# CommonBoard_FK_H743_out.net
KiCad netlist of a schematic drawn in Altium Designer
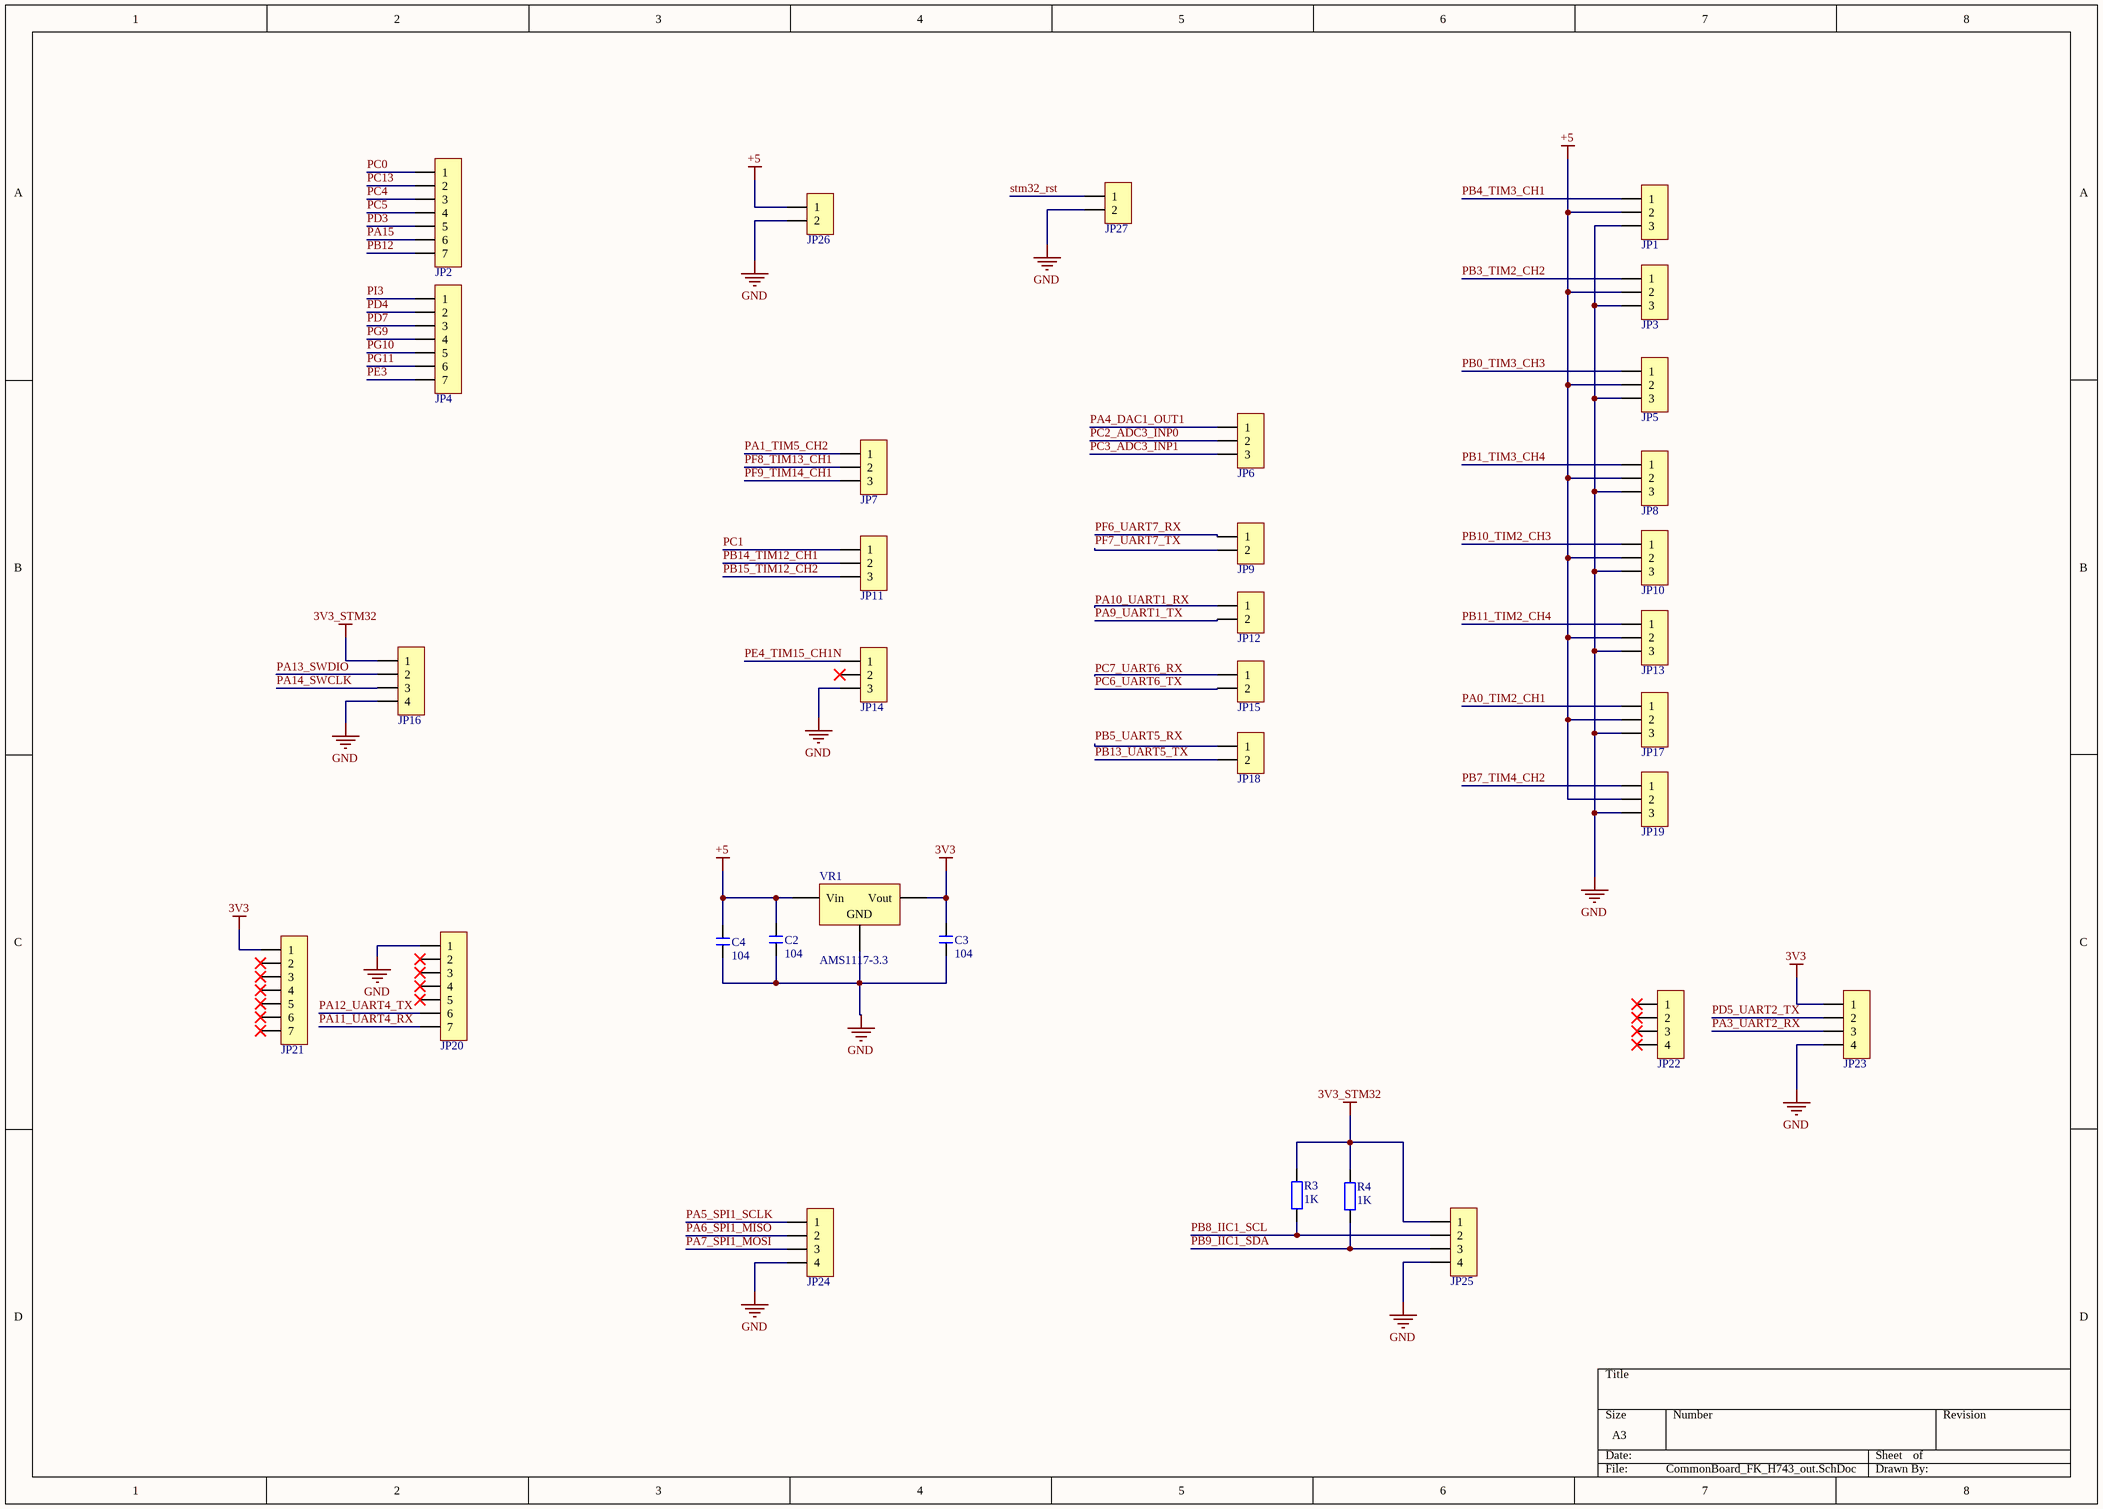
[diagram p0: CommonBoard_FK_H743_out.SchDoc]

(export (version "E")
  (design (tool "Eeschema 10.0.6"))
  (components
    (comp (ref "C2")
      (value "104")
      (footprint "C 0603_L")
      (description "无极性贴片电容")
      (fields (field (name "版权归属") "源创客"))
      (libsource (lib "3.1   - 电阻-电容-电感") (part "C"))
    )
    (comp (ref "C3")
      (value "104")
      (footprint "C 0603_L")
      (description "无极性贴片电容")
      (fields (field (name "版权归属") "源创客"))
      (libsource (lib "3.1   - 电阻-电容-电感") (part "C"))
    )
    (comp (ref "C4")
      (value "104")
      (footprint "C 0603_L")
      (description "无极性贴片电容")
      (fields (field (name "版权归属") "源创客"))
      (libsource (lib "3.1   - 电阻-电容-电感") (part "C"))
    )
    (comp (ref "JP1")
      (value "HDR-1X3")
      (footprint "HDR2.54-LI-3P")
      (description "3P接插件")
      (fields (field (name "版权归属") "源创客"))
      (libsource (lib "4.5   - 接插件-脚距2.54") (part "Header 3"))
    )
    (comp (ref "JP2")
      (value "HDR-1X7")
      (footprint "HDR2.54-LI-7P")
      (description "7P接插件")
      (fields (field (name "版权归属") "源创客"))
      (libsource (lib "4.5   - 接插件-脚距2.54") (part "Header 7"))
    )
    (comp (ref "JP3")
      (value "HDR-1X3")
      (footprint "HDR2.54-LI-3P")
      (description "3P接插件")
      (fields (field (name "版权归属") "源创客"))
      (libsource (lib "4.5   - 接插件-脚距2.54") (part "Header 3"))
    )
    (comp (ref "JP4")
      (value "HDR-1X7")
      (footprint "HDR2.54-LI-7P")
      (description "7P接插件")
      (fields (field (name "版权归属") "源创客"))
      (libsource (lib "4.5   - 接插件-脚距2.54") (part "Header 7"))
    )
    (comp (ref "JP5")
      (value "HDR-1X3")
      (footprint "HDR2.54-LI-3P")
      (description "3P接插件")
      (fields (field (name "版权归属") "源创客"))
      (libsource (lib "4.5   - 接插件-脚距2.54") (part "Header 3"))
    )
    (comp (ref "JP6")
      (value "HDR-1X3")
      (footprint "HDR2.54-LI-3P")
      (description "3P接插件")
      (fields (field (name "版权归属") "源创客"))
      (libsource (lib "4.5   - 接插件-脚距2.54") (part "Header 3"))
    )
    (comp (ref "JP7")
      (value "HDR-1X3")
      (footprint "HDR2.54-LI-3P")
      (description "3P接插件")
      (fields (field (name "版权归属") "源创客"))
      (libsource (lib "4.5   - 接插件-脚距2.54") (part "Header 3"))
    )
    (comp (ref "JP8")
      (value "HDR-1X3")
      (footprint "HDR2.54-LI-3P")
      (description "3P接插件")
      (fields (field (name "版权归属") "源创客"))
      (libsource (lib "4.5   - 接插件-脚距2.54") (part "Header 3"))
    )
    (comp (ref "JP9")
      (value "HDR-1X2")
      (footprint "HDR2.54-LI-2P")
      (description "2P接插件")
      (fields (field (name "版权归属") "源创客"))
      (libsource (lib "4.5   - 接插件-脚距2.54") (part "Header 2"))
    )
    (comp (ref "JP10")
      (value "HDR-1X3")
      (footprint "HDR2.54-LI-3P")
      (description "3P接插件")
      (fields (field (name "版权归属") "源创客"))
      (libsource (lib "4.5   - 接插件-脚距2.54") (part "Header 3"))
    )
    (comp (ref "JP11")
      (value "HDR-1X3")
      (footprint "HDR2.54-LI-3P")
      (description "3P接插件")
      (fields (field (name "版权归属") "源创客"))
      (libsource (lib "4.5   - 接插件-脚距2.54") (part "Header 3"))
    )
    (comp (ref "JP12")
      (value "HDR-1X2")
      (footprint "HDR2.54-LI-2P")
      (description "2P接插件")
      (fields (field (name "版权归属") "源创客"))
      (libsource (lib "4.5   - 接插件-脚距2.54") (part "Header 2"))
    )
    (comp (ref "JP13")
      (value "HDR-1X3")
      (footprint "HDR2.54-LI-3P")
      (description "3P接插件")
      (fields (field (name "版权归属") "源创客"))
      (libsource (lib "4.5   - 接插件-脚距2.54") (part "Header 3"))
    )
    (comp (ref "JP14")
      (value "HDR-1X3")
      (footprint "HDR2.54-LI-3P")
      (description "3P接插件")
      (fields (field (name "版权归属") "源创客"))
      (libsource (lib "4.5   - 接插件-脚距2.54") (part "Header 3"))
    )
    (comp (ref "JP15")
      (value "HDR-1X2")
      (footprint "HDR2.54-LI-2P")
      (description "2P接插件")
      (fields (field (name "版权归属") "源创客"))
      (libsource (lib "4.5   - 接插件-脚距2.54") (part "Header 2"))
    )
    (comp (ref "JP16")
      (value "HDR-1X4")
      (footprint "HDR2.54-LI-4P")
      (description "4P接插件")
      (fields (field (name "版权归属") "源创客"))
      (libsource (lib "4.5   - 接插件-脚距2.54") (part "Header 4"))
    )
    (comp (ref "JP17")
      (value "HDR-1X3")
      (footprint "HDR2.54-LI-3P")
      (description "3P接插件")
      (fields (field (name "版权归属") "源创客"))
      (libsource (lib "4.5   - 接插件-脚距2.54") (part "Header 3"))
    )
    (comp (ref "JP18")
      (value "HDR-1X2")
      (footprint "HDR2.54-LI-2P")
      (description "2P接插件")
      (fields (field (name "版权归属") "源创客"))
      (libsource (lib "4.5   - 接插件-脚距2.54") (part "Header 2"))
    )
    (comp (ref "JP19")
      (value "HDR-1X3")
      (footprint "HDR2.54-LI-3P")
      (description "3P接插件")
      (fields (field (name "版权归属") "源创客"))
      (libsource (lib "4.5   - 接插件-脚距2.54") (part "Header 3"))
    )
    (comp (ref "JP20")
      (value "HDR-1X7")
      (footprint "HDR2.54-LI-7P")
      (description "7P接插件")
      (fields (field (name "版权归属") "源创客"))
      (libsource (lib "4.5   - 接插件-脚距2.54") (part "Header 7"))
    )
    (comp (ref "JP21")
      (value "HDR-1X7")
      (footprint "HDR2.54-LI-7P")
      (description "7P接插件")
      (fields (field (name "版权归属") "源创客"))
      (libsource (lib "4.5   - 接插件-脚距2.54") (part "Header 7"))
    )
    (comp (ref "JP22")
      (value "HDR-1X4")
      (footprint "HDR2.54-LI-4P")
      (description "4P接插件")
      (fields (field (name "版权归属") "源创客"))
      (libsource (lib "4.5   - 接插件-脚距2.54") (part "Header 4"))
    )
    (comp (ref "JP23")
      (value "HDR-1X4")
      (footprint "HDR2.54-LI-4P")
      (description "4P接插件")
      (fields (field (name "版权归属") "源创客"))
      (libsource (lib "4.5   - 接插件-脚距2.54") (part "Header 4"))
    )
    (comp (ref "JP24")
      (value "HDR-1X4")
      (footprint "HDR2.54-LI-4P")
      (description "4P接插件")
      (fields (field (name "版权归属") "源创客"))
      (libsource (lib "4.5   - 接插件-脚距2.54") (part "Header 4"))
    )
    (comp (ref "JP25")
      (value "HDR-1X4")
      (footprint "HDR2.54-LI-4P")
      (description "4P接插件")
      (fields (field (name "版权归属") "源创客"))
      (libsource (lib "4.5   - 接插件-脚距2.54") (part "Header 4"))
    )
    (comp (ref "JP26")
      (value "HDR-1X2")
      (footprint "KF128-3.81-2P")
      (description "2P接插件")
      (fields (field (name "版权归属") "源创客"))
      (libsource (lib "4.7   - 接插件-脚距3.81") (part "Header 2"))
    )
    (comp (ref "JP27")
      (value "HDR-1X2")
      (footprint "HDR2.54-LI-2P")
      (description "2P接插件")
      (fields (field (name "版权归属") "源创客"))
      (libsource (lib "4.5   - 接插件-脚距2.54") (part "Header 2"))
    )
    (comp (ref "R3")
      (value "1K")
      (footprint "R 0603_L")
      (description "贴片电阻")
      (fields (field (name "版权归属") "源创客"))
      (libsource (lib "3.1   - 电阻-电容-电感") (part "R"))
    )
    (comp (ref "R4")
      (value "1K")
      (footprint "R 0603_L")
      (description "贴片电阻")
      (fields (field (name "版权归属") "源创客"))
      (libsource (lib "3.1   - 电阻-电容-电感") (part "R"))
    )
    (comp (ref "VR1")
      (value "AMS1117-3.3")
      (footprint "SOT-223")
      (description "低压差线性稳压(LDO)")
      (libsource (lib "Miscellaneous Devices LC") (part "SOT-223 AMS1117-3.3"))
    )
  )
  (nets
    (net (code "1") (name "+5") (class "Default")
      (node (ref "C2") (pin "2") (pinfunction "2_2") (pintype "passive"))
      (node (ref "C4") (pin "2") (pinfunction "2_2") (pintype "passive"))
      (node (ref "JP1") (pin "2") (pinfunction "2_2") (pintype "passive"))
      (node (ref "JP10") (pin "2") (pinfunction "2_2") (pintype "passive"))
      (node (ref "JP13") (pin "2") (pinfunction "2_2") (pintype "passive"))
      (node (ref "JP17") (pin "2") (pinfunction "2_2") (pintype "passive"))
      (node (ref "JP19") (pin "2") (pinfunction "2_2") (pintype "passive"))
      (node (ref "JP26") (pin "1") (pinfunction "1_1") (pintype "passive"))
      (node (ref "JP3") (pin "2") (pinfunction "2_2") (pintype "passive"))
      (node (ref "JP5") (pin "2") (pinfunction "2_2") (pintype "passive"))
      (node (ref "JP8") (pin "2") (pinfunction "2_2") (pintype "passive"))
      (node (ref "VR1") (pin "3") (pinfunction "Vin_3") (pintype "passive"))
    )
    (net (code "2") (name "/PA0_TIM2_CH1") (class "Default")
      (node (ref "JP17") (pin "1") (pinfunction "1_1") (pintype "passive"))
    )
    (net (code "3") (name "/PA1_TIM5_CH2") (class "Default")
      (node (ref "JP7") (pin "1") (pinfunction "1_1") (pintype "passive"))
    )
    (net (code "4") (name "/PA3_UART2_RX") (class "Default")
      (node (ref "JP23") (pin "3") (pinfunction "3_3") (pintype "passive"))
    )
    (net (code "5") (name "/PA4_DAC1_OUT1") (class "Default")
      (node (ref "JP6") (pin "1") (pinfunction "1_1") (pintype "passive"))
    )
    (net (code "6") (name "/PA5_SPI1_SCLK") (class "Default")
      (node (ref "JP24") (pin "1") (pinfunction "1_1") (pintype "passive"))
    )
    (net (code "7") (name "/PA6_SPI1_MISO") (class "Default")
      (node (ref "JP24") (pin "2") (pinfunction "2_2") (pintype "passive"))
    )
    (net (code "8") (name "/PA7_SPI1_MOSI") (class "Default")
      (node (ref "JP24") (pin "3") (pinfunction "3_3") (pintype "passive"))
    )
    (net (code "9") (name "/PA9_UART1_TX") (class "Default")
      (node (ref "JP12") (pin "2") (pinfunction "2_2") (pintype "passive"))
    )
    (net (code "10") (name "/PA10_UART1_RX") (class "Default")
      (node (ref "JP12") (pin "1") (pinfunction "1_1") (pintype "passive"))
    )
    (net (code "11") (name "/PA11_UART4_RX") (class "Default")
      (node (ref "JP20") (pin "7") (pinfunction "7_7") (pintype "passive"))
    )
    (net (code "12") (name "/PA12_UART4_TX") (class "Default")
      (node (ref "JP20") (pin "6") (pinfunction "6_6") (pintype "passive"))
    )
    (net (code "13") (name "/PA13_SWDIO") (class "Default")
      (node (ref "JP16") (pin "2") (pinfunction "2_2") (pintype "passive"))
    )
    (net (code "14") (name "/PA14_SWCLK") (class "Default")
      (node (ref "JP16") (pin "3") (pinfunction "3_3") (pintype "passive"))
    )
    (net (code "15") (name "/PA15") (class "Default")
      (node (ref "JP2") (pin "6") (pinfunction "6_6") (pintype "passive"))
    )
    (net (code "16") (name "/PB0_TIM3_CH3") (class "Default")
      (node (ref "JP5") (pin "1") (pinfunction "1_1") (pintype "passive"))
    )
    (net (code "17") (name "/PB1_TIM3_CH4") (class "Default")
      (node (ref "JP8") (pin "1") (pinfunction "1_1") (pintype "passive"))
    )
    (net (code "18") (name "/PB3_TIM2_CH2") (class "Default")
      (node (ref "JP3") (pin "1") (pinfunction "1_1") (pintype "passive"))
    )
    (net (code "19") (name "/PB4_TIM3_CH1") (class "Default")
      (node (ref "JP1") (pin "1") (pinfunction "1_1") (pintype "passive"))
    )
    (net (code "20") (name "/PB5_UART5_RX") (class "Default")
      (node (ref "JP18") (pin "1") (pinfunction "1_1") (pintype "passive"))
    )
    (net (code "21") (name "/PB7_TIM4_CH2") (class "Default")
      (node (ref "JP19") (pin "1") (pinfunction "1_1") (pintype "passive"))
    )
    (net (code "22") (name "/PB8_IIC1_SCL") (class "Default")
      (node (ref "JP25") (pin "2") (pinfunction "2_2") (pintype "passive"))
      (node (ref "R3") (pin "2") (pinfunction "2_2") (pintype "passive"))
    )
    (net (code "23") (name "/PB9_IIC1_SDA") (class "Default")
      (node (ref "JP25") (pin "3") (pinfunction "3_3") (pintype "passive"))
      (node (ref "R4") (pin "2") (pinfunction "2_2") (pintype "passive"))
    )
    (net (code "24") (name "/PB10_TIM2_CH3") (class "Default")
      (node (ref "JP10") (pin "1") (pinfunction "1_1") (pintype "passive"))
    )
    (net (code "25") (name "/PB11_TIM2_CH4") (class "Default")
      (node (ref "JP13") (pin "1") (pinfunction "1_1") (pintype "passive"))
    )
    (net (code "26") (name "/PB12") (class "Default")
      (node (ref "JP2") (pin "7") (pinfunction "7_7") (pintype "passive"))
    )
    (net (code "27") (name "/PB13_UART5_TX") (class "Default")
      (node (ref "JP18") (pin "2") (pinfunction "2_2") (pintype "passive"))
    )
    (net (code "28") (name "/PB14_TIM12_CH1") (class "Default")
      (node (ref "JP11") (pin "2") (pinfunction "2_2") (pintype "passive"))
    )
    (net (code "29") (name "/PB15_TIM12_CH2") (class "Default")
      (node (ref "JP11") (pin "3") (pinfunction "3_3") (pintype "passive"))
    )
    (net (code "30") (name "/PC0") (class "Default")
      (node (ref "JP2") (pin "1") (pinfunction "1_1") (pintype "passive"))
    )
    (net (code "31") (name "/PC1") (class "Default")
      (node (ref "JP11") (pin "1") (pinfunction "1_1") (pintype "passive"))
    )
    (net (code "32") (name "/PC2_ADC3_INP0") (class "Default")
      (node (ref "JP6") (pin "2") (pinfunction "2_2") (pintype "passive"))
    )
    (net (code "33") (name "/PC3_ADC3_INP1") (class "Default")
      (node (ref "JP6") (pin "3") (pinfunction "3_3") (pintype "passive"))
    )
    (net (code "34") (name "/PC4") (class "Default")
      (node (ref "JP2") (pin "3") (pinfunction "3_3") (pintype "passive"))
    )
    (net (code "35") (name "/PC5") (class "Default")
      (node (ref "JP2") (pin "4") (pinfunction "4_4") (pintype "passive"))
    )
    (net (code "36") (name "/PC6_UART6_TX") (class "Default")
      (node (ref "JP15") (pin "2") (pinfunction "2_2") (pintype "passive"))
    )
    (net (code "37") (name "/PC7_UART6_RX") (class "Default")
      (node (ref "JP15") (pin "1") (pinfunction "1_1") (pintype "passive"))
    )
    (net (code "38") (name "/PC13") (class "Default")
      (node (ref "JP2") (pin "2") (pinfunction "2_2") (pintype "passive"))
    )
    (net (code "39") (name "/PD3") (class "Default")
      (node (ref "JP2") (pin "5") (pinfunction "5_5") (pintype "passive"))
    )
    (net (code "40") (name "/PD4") (class "Default")
      (node (ref "JP4") (pin "2") (pinfunction "2_2") (pintype "passive"))
    )
    (net (code "41") (name "/PD5_UART2_TX") (class "Default")
      (node (ref "JP23") (pin "2") (pinfunction "2_2") (pintype "passive"))
    )
    (net (code "42") (name "/PD7") (class "Default")
      (node (ref "JP4") (pin "3") (pinfunction "3_3") (pintype "passive"))
    )
    (net (code "43") (name "/PE3") (class "Default")
      (node (ref "JP4") (pin "7") (pinfunction "7_7") (pintype "passive"))
    )
    (net (code "44") (name "/PE4_TIM15_CH1N") (class "Default")
      (node (ref "JP14") (pin "1") (pinfunction "1_1") (pintype "passive"))
    )
    (net (code "45") (name "/PF6_UART7_RX") (class "Default")
      (node (ref "JP9") (pin "1") (pinfunction "1_1") (pintype "passive"))
    )
    (net (code "46") (name "/PF7_UART7_TX") (class "Default")
      (node (ref "JP9") (pin "2") (pinfunction "2_2") (pintype "passive"))
    )
    (net (code "47") (name "/PF8_TIM13_CH1") (class "Default")
      (node (ref "JP7") (pin "2") (pinfunction "2_2") (pintype "passive"))
    )
    (net (code "48") (name "/PF9_TIM14_CH1") (class "Default")
      (node (ref "JP7") (pin "3") (pinfunction "3_3") (pintype "passive"))
    )
    (net (code "49") (name "/PG9") (class "Default")
      (node (ref "JP4") (pin "4") (pinfunction "4_4") (pintype "passive"))
    )
    (net (code "50") (name "/PG10") (class "Default")
      (node (ref "JP4") (pin "5") (pinfunction "5_5") (pintype "passive"))
    )
    (net (code "51") (name "/PG11") (class "Default")
      (node (ref "JP4") (pin "6") (pinfunction "6_6") (pintype "passive"))
    )
    (net (code "52") (name "/PI3") (class "Default")
      (node (ref "JP4") (pin "1") (pinfunction "1_1") (pintype "passive"))
    )
    (net (code "53") (name "/stm32_rst") (class "Default")
      (node (ref "JP27") (pin "1") (pinfunction "1_1") (pintype "passive"))
    )
    (net (code "54") (name "3V3") (class "Default")
      (node (ref "C3") (pin "2") (pinfunction "2_2") (pintype "passive"))
      (node (ref "JP21") (pin "1") (pinfunction "1_1") (pintype "passive"))
      (node (ref "JP23") (pin "1") (pinfunction "1_1") (pintype "passive"))
      (node (ref "VR1") (pin "2") (pinfunction "Vout_2") (pintype "passive"))
    )
    (net (code "55") (name "3V3_STM32") (class "Default")
      (node (ref "JP16") (pin "1") (pinfunction "1_1") (pintype "passive"))
      (node (ref "JP25") (pin "1") (pinfunction "1_1") (pintype "passive"))
      (node (ref "R3") (pin "1") (pinfunction "1_1") (pintype "passive"))
      (node (ref "R4") (pin "1") (pinfunction "1_1") (pintype "passive"))
    )
    (net (code "56") (name "GND") (class "Default")
      (node (ref "C2") (pin "1") (pinfunction "1_1") (pintype "passive"))
      (node (ref "C3") (pin "1") (pinfunction "1_1") (pintype "passive"))
      (node (ref "C4") (pin "1") (pinfunction "1_1") (pintype "passive"))
      (node (ref "JP1") (pin "3") (pinfunction "3_3") (pintype "passive"))
      (node (ref "JP10") (pin "3") (pinfunction "3_3") (pintype "passive"))
      (node (ref "JP13") (pin "3") (pinfunction "3_3") (pintype "passive"))
      (node (ref "JP14") (pin "3") (pinfunction "3_3") (pintype "passive"))
      (node (ref "JP16") (pin "4") (pinfunction "4_4") (pintype "passive"))
      (node (ref "JP17") (pin "3") (pinfunction "3_3") (pintype "passive"))
      (node (ref "JP19") (pin "3") (pinfunction "3_3") (pintype "passive"))
      (node (ref "JP20") (pin "1") (pinfunction "1_1") (pintype "passive"))
      (node (ref "JP23") (pin "4") (pinfunction "4_4") (pintype "passive"))
      (node (ref "JP24") (pin "4") (pinfunction "4_4") (pintype "passive"))
      (node (ref "JP25") (pin "4") (pinfunction "4_4") (pintype "passive"))
      (node (ref "JP26") (pin "2") (pinfunction "2_2") (pintype "passive"))
      (node (ref "JP27") (pin "2") (pinfunction "2_2") (pintype "passive"))
      (node (ref "JP3") (pin "3") (pinfunction "3_3") (pintype "passive"))
      (node (ref "JP5") (pin "3") (pinfunction "3_3") (pintype "passive"))
      (node (ref "JP8") (pin "3") (pinfunction "3_3") (pintype "passive"))
      (node (ref "VR1") (pin "1") (pinfunction "GND_1") (pintype "passive"))
    )
    (net (code "57") (name "unconnected-(JP14-Pad2)") (class "Default")
      (node (ref "JP14") (pin "2") (pinfunction "2_2") (pintype "passive+no_connect"))
    )
    (net (code "58") (name "unconnected-(JP20-Pad2)") (class "Default")
      (node (ref "JP20") (pin "2") (pinfunction "2_2") (pintype "passive+no_connect"))
    )
    (net (code "59") (name "unconnected-(JP20-Pad3)") (class "Default")
      (node (ref "JP20") (pin "3") (pinfunction "3_3") (pintype "passive+no_connect"))
    )
    (net (code "60") (name "unconnected-(JP20-Pad4)") (class "Default")
      (node (ref "JP20") (pin "4") (pinfunction "4_4") (pintype "passive+no_connect"))
    )
    (net (code "61") (name "unconnected-(JP20-Pad5)") (class "Default")
      (node (ref "JP20") (pin "5") (pinfunction "5_5") (pintype "passive+no_connect"))
    )
    (net (code "62") (name "unconnected-(JP21-Pad2)") (class "Default")
      (node (ref "JP21") (pin "2") (pinfunction "2_2") (pintype "passive+no_connect"))
    )
    (net (code "63") (name "unconnected-(JP21-Pad3)") (class "Default")
      (node (ref "JP21") (pin "3") (pinfunction "3_3") (pintype "passive+no_connect"))
    )
    (net (code "64") (name "unconnected-(JP21-Pad4)") (class "Default")
      (node (ref "JP21") (pin "4") (pinfunction "4_4") (pintype "passive+no_connect"))
    )
    (net (code "65") (name "unconnected-(JP21-Pad5)") (class "Default")
      (node (ref "JP21") (pin "5") (pinfunction "5_5") (pintype "passive+no_connect"))
    )
    (net (code "66") (name "unconnected-(JP21-Pad6)") (class "Default")
      (node (ref "JP21") (pin "6") (pinfunction "6_6") (pintype "passive+no_connect"))
    )
    (net (code "67") (name "unconnected-(JP21-Pad7)") (class "Default")
      (node (ref "JP21") (pin "7") (pinfunction "7_7") (pintype "passive+no_connect"))
    )
    (net (code "68") (name "unconnected-(JP22-Pad1)") (class "Default")
      (node (ref "JP22") (pin "1") (pinfunction "1_1") (pintype "passive+no_connect"))
    )
    (net (code "69") (name "unconnected-(JP22-Pad2)") (class "Default")
      (node (ref "JP22") (pin "2") (pinfunction "2_2") (pintype "passive+no_connect"))
    )
    (net (code "70") (name "unconnected-(JP22-Pad3)") (class "Default")
      (node (ref "JP22") (pin "3") (pinfunction "3_3") (pintype "passive+no_connect"))
    )
    (net (code "71") (name "unconnected-(JP22-Pad4)") (class "Default")
      (node (ref "JP22") (pin "4") (pinfunction "4_4") (pintype "passive+no_connect"))
    )
  )
)
